# -46342_21-004_3_1.net
KiCad netlist of a schematic drawn in Altium Designer
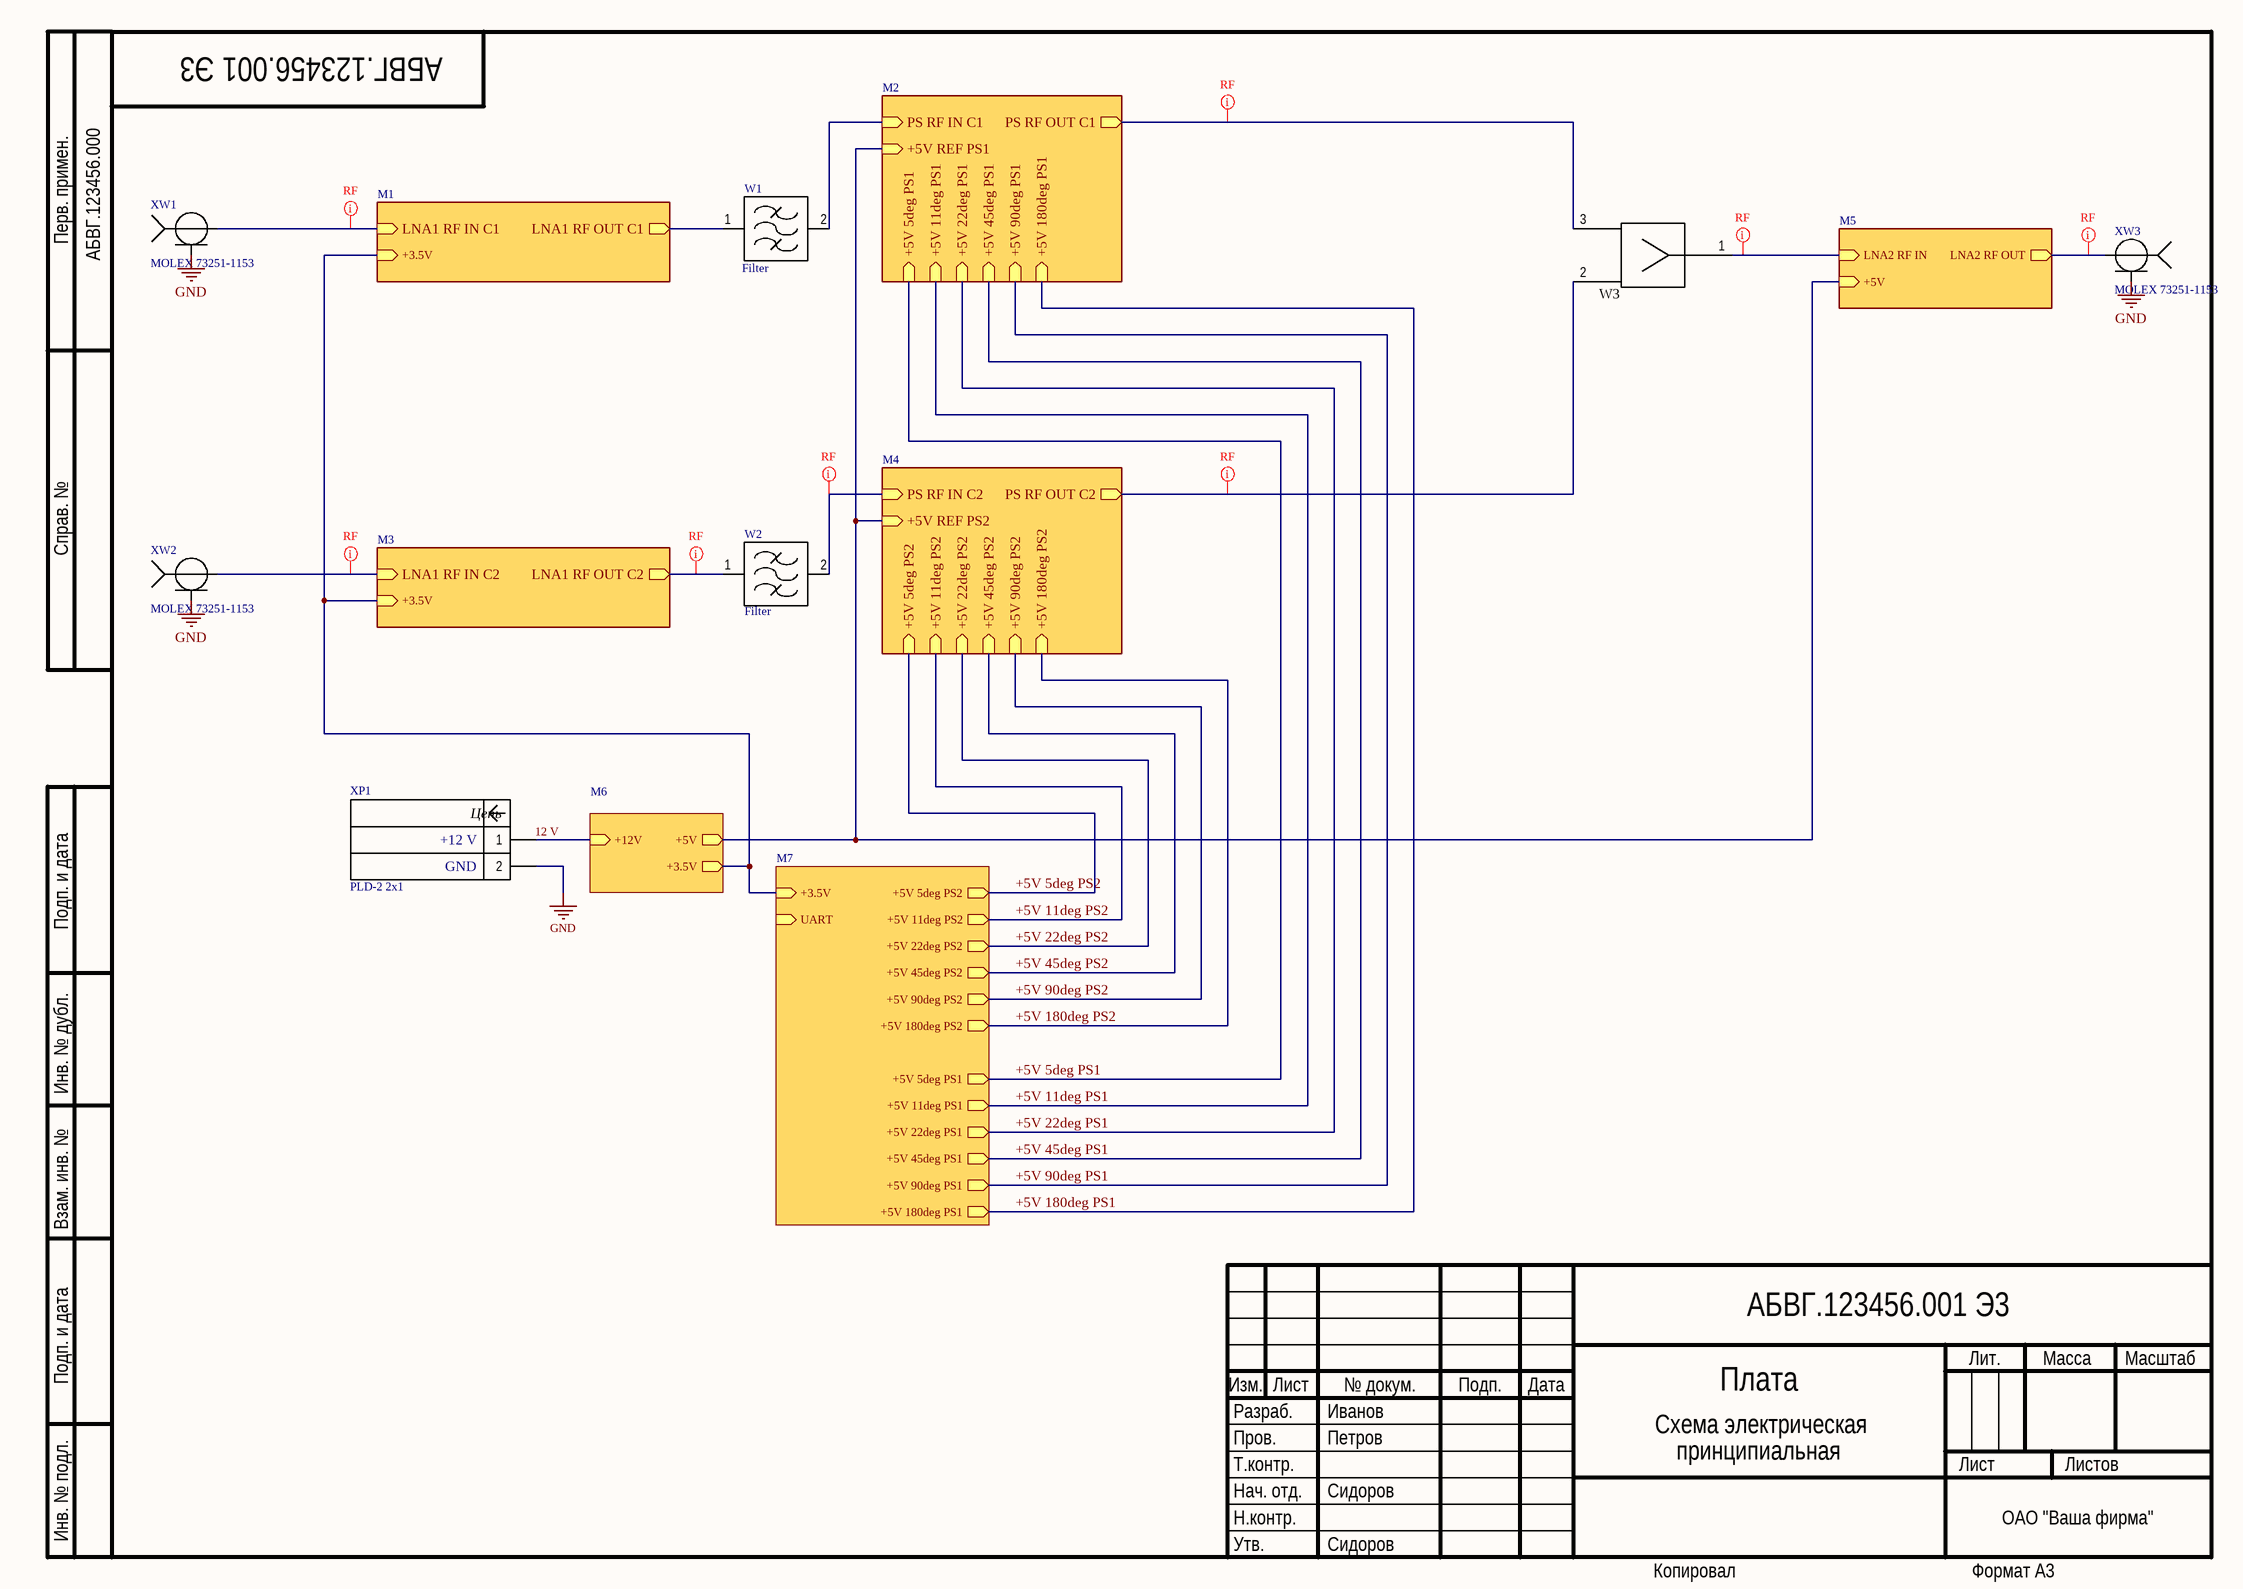
[diagram p0: МПСУ-46342.21-004 Э3 Лист1.SchDoc]

(export (version "E")
  (design (tool "Eeschema 10.0.6"))
  (components
    (comp (ref "W1") (value "Filter") (footprint "Filter") (libsource (lib "MLIN") (part "Filter")))
    (comp (ref "W2") (value "Filter") (footprint "Filter") (libsource (lib "MLIN") (part "Filter")))
    (comp (ref "W3")
      (value "Wilkinson Coupler")
      (footprint "CouplerWilk")
      (description "Wilkinson Coupler diel 7.2GHz, RO4003, h=0.2mm")
      (libsource (lib "receiver") (part "CouplerWilk"))
    )
    (comp (ref "XP1")
      (value "PLD-2 2x1")
      (footprint "HDRV2W64P254_1X2_254X508H884")
      (description "Header, Vertical, Non-shrouded, 2.54 mm pitch 2x1")
      (fields (field (name "NET1") "+12 V") (field (name "NET2") "GND"))
      (libsource (lib "receiver") (part "PLD-2"))
    )
    (comp (ref "XW1")
      (value "MOLEX 73251-1153")
      (footprint "MOLEX 73251-1153 - 1.1pin")
      (description "MOLEX 73251-1153 (SMA EDGE)")
      (fields (field (name "MANUFACTURER") "Molex"))
      (libsource (lib "receiver") (part "MOLEX 73251-1153"))
    )
    (comp (ref "XW2")
      (value "MOLEX 73251-1153")
      (footprint "MOLEX 73251-1153 - 1.1pin")
      (description "MOLEX 73251-1153 (SMA EDGE)")
      (fields (field (name "MANUFACTURER") "Molex"))
      (libsource (lib "receiver") (part "MOLEX 73251-1153"))
    )
    (comp (ref "XW3")
      (value "MOLEX 73251-1153")
      (footprint "MOLEX 73251-1153 - 1.1pin")
      (description "MOLEX 73251-1153 (SMA EDGE)")
      (fields (field (name "MANUFACTURER") "Molex"))
      (libsource (lib "receiver") (part "MOLEX 73251-1153"))
    )
  )
  (nets
    (net (code "15") (name "/12 V") (class "Default")
      (node (ref "XP1") (pin "1") (pinfunction "1_1") (pintype "passive"))
    )
    (net (code "16") (name "/LNA1 RF IN C1") (class "Default")
      (node (ref "XW1") (pin "1") (pinfunction "1_1") (pintype "passive"))
    )
    (net (code "17") (name "/LNA1 RF IN C2") (class "Default")
      (node (ref "XW2") (pin "1") (pinfunction "1_1") (pintype "passive"))
    )
    (net (code "18") (name "/LNA1 RF OUT C1") (class "Default")
      (node (ref "W1") (pin "1") (pinfunction "1_1") (pintype "passive"))
    )
    (net (code "19") (name "/LNA1 RF OUT C2") (class "Default")
      (node (ref "W2") (pin "1") (pinfunction "1_1") (pintype "passive"))
    )
    (net (code "20") (name "/LNA2 RF IN") (class "Default")
      (node (ref "W3") (pin "1") (pinfunction "1_1") (pintype "passive"))
    )
    (net (code "21") (name "/LNA2 RF OUT") (class "Default")
      (node (ref "XW3") (pin "1") (pinfunction "1_1") (pintype "passive"))
    )
    (net (code "22") (name "/PS RF IN C1") (class "Default")
      (node (ref "W1") (pin "2") (pinfunction "2_2") (pintype "passive"))
    )
    (net (code "23") (name "/PS RF IN C2") (class "Default")
      (node (ref "W2") (pin "2") (pinfunction "2_2") (pintype "passive"))
    )
    (net (code "24") (name "/PS RF OUT C1") (class "Default")
      (node (ref "W3") (pin "3") (pinfunction "3_3") (pintype "passive"))
    )
    (net (code "25") (name "/PS RF OUT C2") (class "Default")
      (node (ref "W3") (pin "2") (pinfunction "2_2") (pintype "passive"))
    )
    (net (code "27") (name "GND") (class "Default")
      (node (ref "XP1") (pin "2") (pinfunction "2_2") (pintype "passive"))
      (node (ref "XW1") (pin "2") (pinfunction "2_2") (pintype "passive"))
      (node (ref "XW2") (pin "2") (pinfunction "2_2") (pintype "passive"))
      (node (ref "XW3") (pin "2") (pinfunction "2_2") (pintype "passive"))
    )
  )
)
